# top.net
KiCad netlist of a schematic drawn in EAGLE
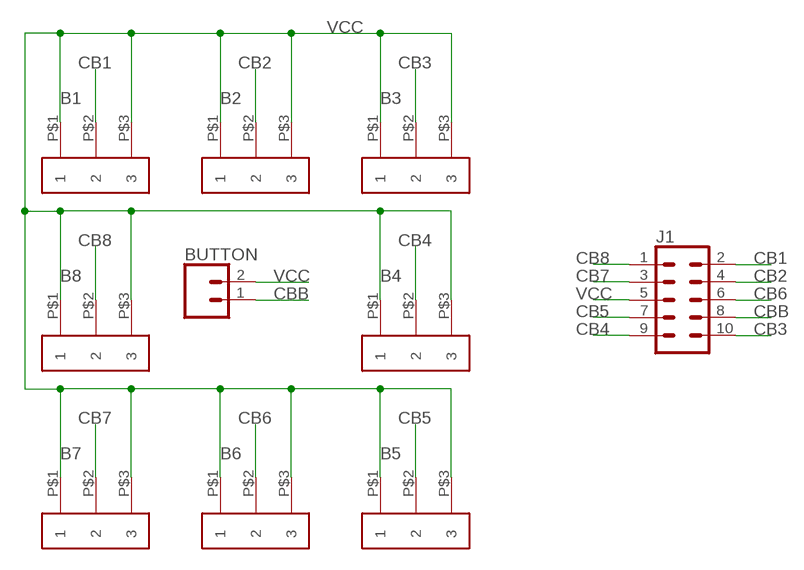
[diagram p0: schematic, sheet 1]

(export (version "E")
  (design (tool "Eeschema 10.0.6"))
  (components
    (comp (ref "B1")
      (value "BOCAL")
      (footprint "eagle-import:BOCAL")
      (libsource (lib "eagle-import") (part "BOCAL"))
    )
    (comp (ref "B2")
      (value "BOCAL")
      (footprint "eagle-import:BOCAL")
      (libsource (lib "eagle-import") (part "BOCAL"))
    )
    (comp (ref "B3")
      (value "BOCAL")
      (footprint "eagle-import:BOCAL")
      (libsource (lib "eagle-import") (part "BOCAL"))
    )
    (comp (ref "B4")
      (value "BOCAL")
      (footprint "eagle-import:BOCAL")
      (libsource (lib "eagle-import") (part "BOCAL"))
    )
    (comp (ref "B5")
      (value "BOCAL")
      (footprint "eagle-import:BOCAL")
      (libsource (lib "eagle-import") (part "BOCAL"))
    )
    (comp (ref "B6")
      (value "BOCAL")
      (footprint "eagle-import:BOCAL")
      (libsource (lib "eagle-import") (part "BOCAL"))
    )
    (comp (ref "B7")
      (value "BOCAL")
      (footprint "eagle-import:BOCAL")
      (libsource (lib "eagle-import") (part "BOCAL"))
    )
    (comp (ref "B8")
      (value "BOCAL")
      (footprint "eagle-import:BOCAL")
      (libsource (lib "eagle-import") (part "BOCAL"))
    )
    (comp (ref "BUTTON")
      (value "CONN_02")
      (footprint "eagle-import:1X02")
      (libsource (lib "eagle-import") (part "CONN_02"))
    )
    (comp (ref "J1")
      (value "CONN_05X2NO_SILK")
      (footprint "eagle-import:2X5_NOSILK")
      (libsource (lib "eagle-import") (part "CONN_05X2NO_SILK"))
    )
  )
  (nets
    (net (code "1") (name "/CB1") (class "Default")
      (node (ref "B1") (pin "P$2") (pinfunction "2_P$2") (pintype "bidirectional"))
      (node (ref "J1") (pin "2") (pinfunction "2_2") (pintype "passive"))
    )
    (net (code "2") (name "/CB2") (class "Default")
      (node (ref "B2") (pin "P$2") (pinfunction "2_P$2") (pintype "bidirectional"))
      (node (ref "J1") (pin "4") (pinfunction "4_4") (pintype "passive"))
    )
    (net (code "3") (name "/CB3") (class "Default")
      (node (ref "B3") (pin "P$2") (pinfunction "2_P$2") (pintype "bidirectional"))
      (node (ref "J1") (pin "10") (pinfunction "10_10") (pintype "passive"))
    )
    (net (code "4") (name "/CB4") (class "Default")
      (node (ref "B4") (pin "P$2") (pinfunction "2_P$2") (pintype "bidirectional"))
      (node (ref "J1") (pin "9") (pinfunction "9_9") (pintype "passive"))
    )
    (net (code "5") (name "/CB5") (class "Default")
      (node (ref "B5") (pin "P$2") (pinfunction "2_P$2") (pintype "bidirectional"))
      (node (ref "J1") (pin "7") (pinfunction "7_7") (pintype "passive"))
    )
    (net (code "6") (name "/CB6") (class "Default")
      (node (ref "B6") (pin "P$2") (pinfunction "2_P$2") (pintype "bidirectional"))
      (node (ref "J1") (pin "6") (pinfunction "6_6") (pintype "passive"))
    )
    (net (code "7") (name "/CB7") (class "Default")
      (node (ref "B7") (pin "P$2") (pinfunction "2_P$2") (pintype "bidirectional"))
      (node (ref "J1") (pin "3") (pinfunction "3_3") (pintype "passive"))
    )
    (net (code "8") (name "/CB8") (class "Default")
      (node (ref "B8") (pin "P$2") (pinfunction "2_P$2") (pintype "bidirectional"))
      (node (ref "J1") (pin "1") (pinfunction "1_1") (pintype "passive"))
    )
    (net (code "9") (name "/CBB") (class "Default")
      (node (ref "BUTTON") (pin "1") (pinfunction "1_1") (pintype "passive"))
      (node (ref "J1") (pin "8") (pinfunction "8_8") (pintype "passive"))
    )
    (net (code "10") (name "/VCC") (class "Default")
      (node (ref "B1") (pin "P$1") (pinfunction "1_P$1") (pintype "bidirectional"))
      (node (ref "B1") (pin "P$3") (pinfunction "3_P$3") (pintype "bidirectional"))
      (node (ref "B2") (pin "P$1") (pinfunction "1_P$1") (pintype "bidirectional"))
      (node (ref "B2") (pin "P$3") (pinfunction "3_P$3") (pintype "bidirectional"))
      (node (ref "B3") (pin "P$1") (pinfunction "1_P$1") (pintype "bidirectional"))
      (node (ref "B3") (pin "P$3") (pinfunction "3_P$3") (pintype "bidirectional"))
      (node (ref "B4") (pin "P$1") (pinfunction "1_P$1") (pintype "bidirectional"))
      (node (ref "B4") (pin "P$3") (pinfunction "3_P$3") (pintype "bidirectional"))
      (node (ref "B5") (pin "P$1") (pinfunction "1_P$1") (pintype "bidirectional"))
      (node (ref "B5") (pin "P$3") (pinfunction "3_P$3") (pintype "bidirectional"))
      (node (ref "B6") (pin "P$1") (pinfunction "1_P$1") (pintype "bidirectional"))
      (node (ref "B6") (pin "P$3") (pinfunction "3_P$3") (pintype "bidirectional"))
      (node (ref "B7") (pin "P$1") (pinfunction "1_P$1") (pintype "bidirectional"))
      (node (ref "B7") (pin "P$3") (pinfunction "3_P$3") (pintype "bidirectional"))
      (node (ref "B8") (pin "P$1") (pinfunction "1_P$1") (pintype "bidirectional"))
      (node (ref "B8") (pin "P$3") (pinfunction "3_P$3") (pintype "bidirectional"))
      (node (ref "BUTTON") (pin "2") (pinfunction "2_2") (pintype "passive"))
      (node (ref "J1") (pin "5") (pinfunction "5_5") (pintype "passive"))
    )
  )
)
